# untitled.net
KiCad netlist of a schematic drawn in EAGLE
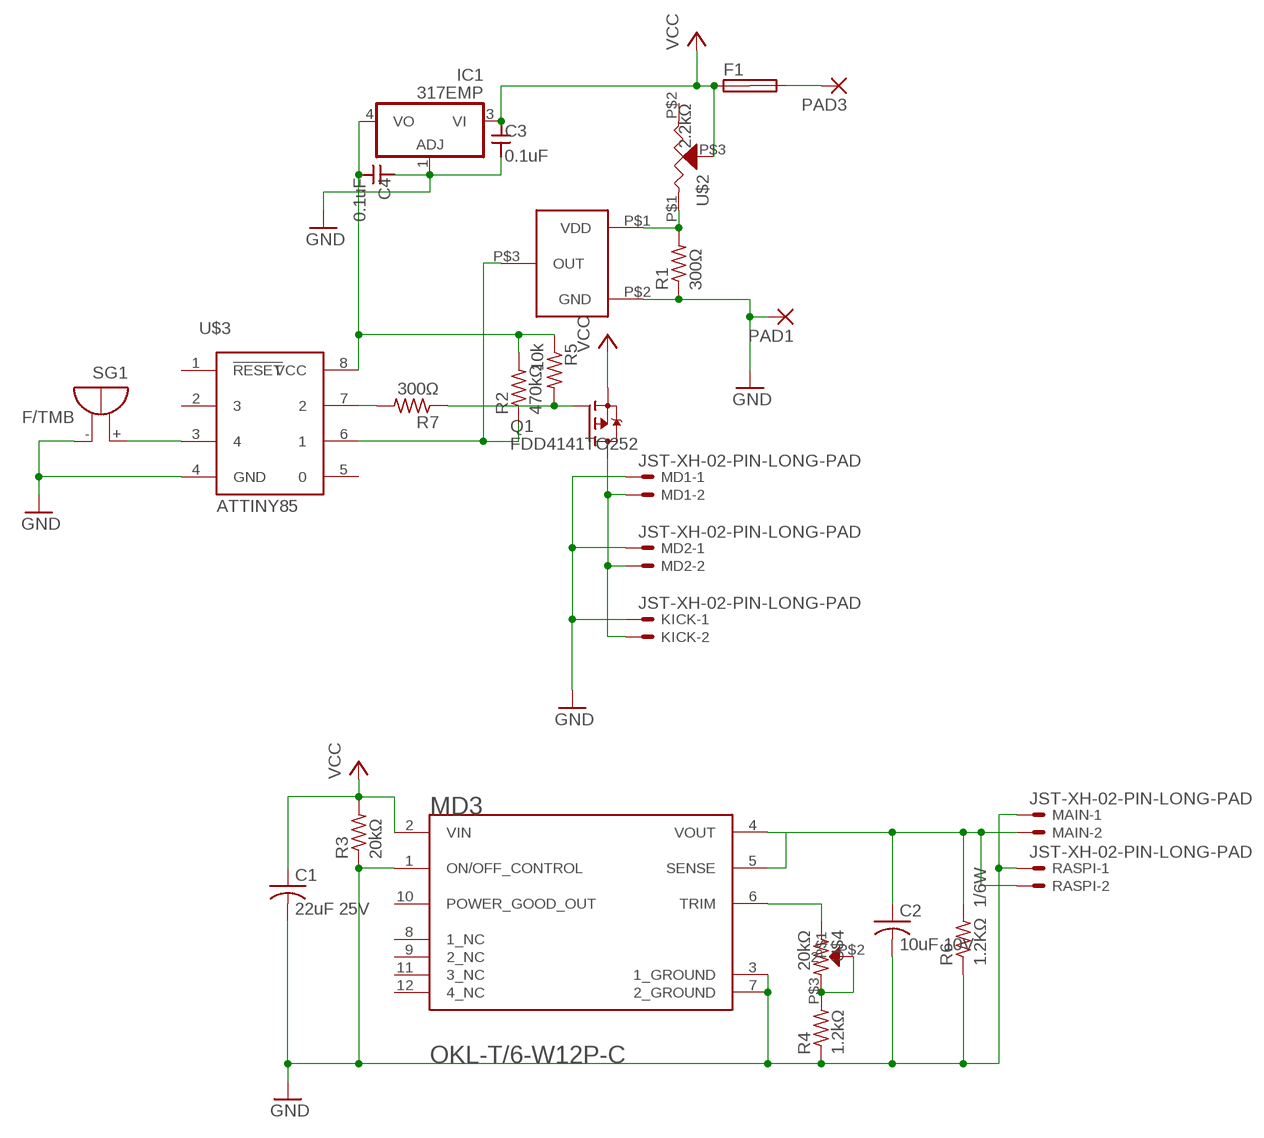
[diagram p0: schematic, sheet 1]

(export (version "E")
  (design (tool "Eeschema 10.0.6"))
  (components
    (comp (ref "C1")
      (value "22uF 25V")
      (footprint "eagle-import:C2012")
      (libsource (lib "eagle-import") (part "C-USC2012"))
    )
    (comp (ref "C2")
      (value "10uF 10V")
      (footprint "eagle-import:C2012")
      (libsource (lib "eagle-import") (part "C-USC2012"))
    )
    (comp (ref "C3")
      (value "0.1uF")
      (footprint "eagle-import:SMD1608")
      (libsource (lib "eagle-import") (part "CAPACITOR1608"))
    )
    (comp (ref "C4")
      (value "0.1uF")
      (footprint "eagle-import:SMD1608")
      (libsource (lib "eagle-import") (part "CAPACITOR1608"))
    )
    (comp (ref "F1")
      (value "SHK20L")
      (footprint "eagle-import:SHK20L")
      (libsource (lib "eagle-import") (part "SHK20L"))
    )
    (comp (ref "IC1")
      (value "317EMP")
      (footprint "eagle-import:SOT223")
      (libsource (lib "eagle-import") (part "317EMP"))
    )
    (comp (ref "KICK")
      (value "JST-XH-02-PIN-LONG-PAD")
      (footprint "eagle-import:JST-XH-02-PACKAGE-LONG-PAD")
      (libsource (lib "eagle-import") (part "JST-XH-02-PIN-LONG-PAD"))
    )
    (comp (ref "MAIN")
      (value "JST-XH-02-PIN-LONG-PAD")
      (footprint "eagle-import:JST-XH-02-PACKAGE-LONG-PAD")
      (libsource (lib "eagle-import") (part "JST-XH-02-PIN-LONG-PAD"))
    )
    (comp (ref "MD1")
      (value "JST-XH-02-PIN-LONG-PAD")
      (footprint "eagle-import:JST-XH-02-PACKAGE-LONG-PAD")
      (libsource (lib "eagle-import") (part "JST-XH-02-PIN-LONG-PAD"))
    )
    (comp (ref "MD2")
      (value "JST-XH-02-PIN-LONG-PAD")
      (footprint "eagle-import:JST-XH-02-PACKAGE-LONG-PAD")
      (libsource (lib "eagle-import") (part "JST-XH-02-PIN-LONG-PAD"))
    )
    (comp (ref "MD3")
      (value "OKL-T/6-W12P-CMURATA_OKL-T-6-W12P-C_0_0")
      (footprint "eagle-import:MURATA_OKL-T-6-W12P-C_0")
      (fields (field (name "MF") "Murata Power Solutions Inc.") (field (name "MP") "OKL-T/6-W12P-C"))
      (libsource (lib "eagle-import") (part "OKL-T/6-W12P-CMURATA_OKL-T-6-W12P-C_0_0"))
    )
    (comp (ref "PAD1")
      (value "3,81/1,4")
      (footprint "eagle-import:3,81_1,4")
      (libsource (lib "eagle-import") (part "3,81/1,4"))
    )
    (comp (ref "PAD3")
      (value "3,81/1,4")
      (footprint "eagle-import:3,81_1,4")
      (libsource (lib "eagle-import") (part "3,81/1,4"))
    )
    (comp (ref "Q1")
      (value "FDD4141TO252")
      (footprint "eagle-import:TO252")
      (libsource (lib "eagle-import") (part "FDD4141TO252"))
    )
    (comp (ref "R1")
      (value "300Ω")
      (footprint "eagle-import:M2012")
      (libsource (lib "eagle-import") (part "R-US_M2012"))
    )
    (comp (ref "R2")
      (value "470kΩ")
      (footprint "eagle-import:M2012")
      (libsource (lib "eagle-import") (part "R-US_M2012"))
    )
    (comp (ref "R3")
      (value "20kΩ")
      (footprint "eagle-import:M2012")
      (libsource (lib "eagle-import") (part "R-US_M2012"))
    )
    (comp (ref "R4")
      (value "1.2kΩ")
      (footprint "eagle-import:M2012")
      (libsource (lib "eagle-import") (part "R-US_M2012"))
    )
    (comp (ref "R5")
      (value "10k")
      (footprint "eagle-import:M2012")
      (libsource (lib "eagle-import") (part "R-US_M2012"))
    )
    (comp (ref "R6")
      (value "1.2KΩ 1/6W")
      (footprint "eagle-import:0805-THM")
      (libsource (lib "eagle-import") (part "FLIPFLOP-RES"))
    )
    (comp (ref "R7")
      (value "300Ω")
      (footprint "eagle-import:M2012")
      (libsource (lib "eagle-import") (part "R-US_M2012"))
    )
    (comp (ref "RASPI")
      (value "JST-XH-02-PIN-LONG-PAD")
      (footprint "eagle-import:JST-XH-02-PACKAGE-LONG-PAD")
      (libsource (lib "eagle-import") (part "JST-XH-02-PIN-LONG-PAD"))
    )
    (comp (ref "SG1")
      (value "F/TMB")
      (footprint "eagle-import:F_TMB")
      (libsource (lib "eagle-import") (part "F/TMB"))
    )
    (comp (ref "U$1")
      (value "R3111N211A")
      (footprint "eagle-import:R3111N211A")
      (libsource (lib "eagle-import") (part "R3111N211A"))
    )
    (comp (ref "U$2")
      (value "2.2kΩ")
      (footprint "eagle-import:SMD-R-TRIM")
      (libsource (lib "eagle-import") (part "SMD-R-TRIM"))
    )
    (comp (ref "U$3")
      (value "ATTINY85")
      (footprint "eagle-import:8P3")
      (libsource (lib "eagle-import") (part "ATTINY85"))
    )
    (comp (ref "U$4")
      (value "20kΩ")
      (footprint "eagle-import:R-TRIM")
      (libsource (lib "eagle-import") (part "R-TRIM"))
    )
  )
  (nets
    (net (code "1") (name "GND") (class "Default")
      (node (ref "C1") (pin "2") (pinfunction "2_2") (pintype "passive"))
      (node (ref "C2") (pin "2") (pinfunction "2_2") (pintype "passive"))
      (node (ref "C3") (pin "2") (pinfunction "2_2") (pintype "passive"))
      (node (ref "C4") (pin "1") (pinfunction "1_1") (pintype "passive"))
      (node (ref "IC1") (pin "1") (pinfunction "ADJ_1") (pintype "input"))
      (node (ref "KICK") (pin "1") (pinfunction "S_1") (pintype "passive"))
      (node (ref "MAIN") (pin "1") (pinfunction "S_1") (pintype "passive"))
      (node (ref "MD1") (pin "1") (pinfunction "S_1") (pintype "passive"))
      (node (ref "MD2") (pin "1") (pinfunction "S_1") (pintype "passive"))
      (node (ref "MD3") (pin "1") (pinfunction "ON/OFF_CONTROL_1") (pintype "input"))
      (node (ref "MD3") (pin "3") (pinfunction "1_GROUND_3") (pintype "power_in"))
      (node (ref "MD3") (pin "7") (pinfunction "2_GROUND_7") (pintype "power_in"))
      (node (ref "PAD1") (pin "1") (pinfunction "P_1") (pintype "passive"))
      (node (ref "R1") (pin "1") (pinfunction "1_1") (pintype "passive"))
      (node (ref "R3") (pin "1") (pinfunction "1_1") (pintype "passive"))
      (node (ref "R4") (pin "1") (pinfunction "1_1") (pintype "passive"))
      (node (ref "R6") (pin "1") (pinfunction "1_1") (pintype "passive"))
      (node (ref "RASPI") (pin "1") (pinfunction "S_1") (pintype "passive"))
      (node (ref "SG1") (pin "-") (pinfunction "-_-") (pintype "passive"))
      (node (ref "U$1") (pin "P$2") (pinfunction "GND_P$2") (pintype "bidirectional"))
      (node (ref "U$3") (pin "4") (pinfunction "GND_4") (pintype "power_in"))
    )
    (net (code "2") (name "Net-(IC1-VO)") (class "Default")
      (node (ref "C4") (pin "2") (pinfunction "2_2") (pintype "passive"))
      (node (ref "IC1") (pin "4") (pinfunction "VO_4") (pintype "passive"))
      (node (ref "R2") (pin "2") (pinfunction "2_2") (pintype "passive"))
      (node (ref "R5") (pin "1") (pinfunction "1_1") (pintype "passive"))
      (node (ref "U$3") (pin "8") (pinfunction "VCC_8") (pintype "power_in"))
    )
    (net (code "3") (name "Net-(KICKB-S)") (class "Default")
      (node (ref "KICK") (pin "2") (pinfunction "S_2") (pintype "passive"))
      (node (ref "MD1") (pin "2") (pinfunction "S_2") (pintype "passive"))
      (node (ref "MD2") (pin "2") (pinfunction "S_2") (pintype "passive"))
      (node (ref "Q1") (pin "3") (pinfunction "D_3") (pintype "passive"))
    )
    (net (code "4") (name "Net-(MAINB-S)") (class "Default")
      (node (ref "C2") (pin "1") (pinfunction "1_1") (pintype "passive"))
      (node (ref "MAIN") (pin "2") (pinfunction "S_2") (pintype "passive"))
      (node (ref "MD3") (pin "4") (pinfunction "VOUT_4") (pintype "power_in"))
      (node (ref "MD3") (pin "5") (pinfunction "SENSE_5") (pintype "passive"))
      (node (ref "R6") (pin "2") (pinfunction "2_2") (pintype "passive"))
      (node (ref "RASPI") (pin "2") (pinfunction "S_2") (pintype "passive"))
    )
    (net (code "5") (name "Net-(MD3-TRIM)") (class "Default")
      (node (ref "MD3") (pin "6") (pinfunction "TRIM_6") (pintype "passive"))
      (node (ref "U$4") (pin "P$1") (pinfunction "1_P$1") (pintype "passive"))
    )
    (net (code "6") (name "Net-(PAD3-P)") (class "Default")
      (node (ref "F1") (pin "2A") (pinfunction "2A_2A") (pintype "passive"))
      (node (ref "PAD3") (pin "1") (pinfunction "P_1") (pintype "passive"))
    )
    (net (code "7") (name "Net-(Q1-G)") (class "Default")
      (node (ref "Q1") (pin "1") (pinfunction "G_1") (pintype "passive"))
      (node (ref "R5") (pin "2") (pinfunction "2_2") (pintype "passive"))
      (node (ref "R7") (pin "1") (pinfunction "1_1") (pintype "passive"))
    )
    (net (code "8") (name "Net-(U$1-OUT)") (class "Default")
      (node (ref "R2") (pin "1") (pinfunction "1_1") (pintype "passive"))
      (node (ref "U$1") (pin "P$3") (pinfunction "OUT_P$3") (pintype "bidirectional"))
      (node (ref "U$3") (pin "6") (pinfunction "1_6") (pintype "bidirectional"))
    )
    (net (code "9") (name "Net-(U$1-VDD)") (class "Default")
      (node (ref "R1") (pin "2") (pinfunction "2_2") (pintype "passive"))
      (node (ref "U$1") (pin "P$1") (pinfunction "VDD_P$1") (pintype "bidirectional"))
      (node (ref "U$2") (pin "P$1") (pinfunction "3_P$1") (pintype "passive"))
    )
    (net (code "10") (name "Net-(U$3-2)") (class "Default")
      (node (ref "R7") (pin "2") (pinfunction "2_2") (pintype "passive"))
      (node (ref "U$3") (pin "7") (pinfunction "2_7") (pintype "bidirectional"))
    )
    (net (code "11") (name "Net-(U$3-4)") (class "Default")
      (node (ref "SG1") (pin "+") (pinfunction "+_+") (pintype "passive"))
      (node (ref "U$3") (pin "3") (pinfunction "4_3") (pintype "bidirectional"))
    )
    (net (code "12") (name "Net-(U$4-2)") (class "Default")
      (node (ref "R4") (pin "2") (pinfunction "2_2") (pintype "passive"))
      (node (ref "U$4") (pin "P$2") (pinfunction "2_P$2") (pintype "bidirectional"))
      (node (ref "U$4") (pin "P$3") (pinfunction "P$1_P$3") (pintype "bidirectional"))
    )
    (net (code "13") (name "VCC") (class "Default")
      (node (ref "C1") (pin "1") (pinfunction "1_1") (pintype "passive"))
      (node (ref "C3") (pin "1") (pinfunction "1_1") (pintype "passive"))
      (node (ref "F1") (pin "1A") (pinfunction "1A_1A") (pintype "passive"))
      (node (ref "IC1") (pin "3") (pinfunction "VI_3") (pintype "input"))
      (node (ref "MD3") (pin "2") (pinfunction "VIN_2") (pintype "power_in"))
      (node (ref "Q1") (pin "2") (pinfunction "S_2") (pintype "passive"))
      (node (ref "R3") (pin "2") (pinfunction "2_2") (pintype "passive"))
      (node (ref "U$2") (pin "P$3") (pinfunction "2_P$3") (pintype "passive"))
    )
    (net (code "14") (name "unconnected-(F1-Pad1B)") (class "Default")
      (node (ref "F1") (pin "1B") (pinfunction "1B_1B") (pintype "passive"))
    )
    (net (code "15") (name "unconnected-(F1-Pad2B)") (class "Default")
      (node (ref "F1") (pin "2B") (pinfunction "2B_2B") (pintype "passive"))
    )
    (net (code "16") (name "unconnected-(MD3-1_NC-Pad8)") (class "Default")
      (node (ref "MD3") (pin "8") (pinfunction "1_NC_8") (pintype "passive"))
    )
    (net (code "17") (name "unconnected-(MD3-2_NC-Pad9)") (class "Default")
      (node (ref "MD3") (pin "9") (pinfunction "2_NC_9") (pintype "passive"))
    )
    (net (code "18") (name "unconnected-(MD3-3_NC-Pad11)") (class "Default")
      (node (ref "MD3") (pin "11") (pinfunction "3_NC_11") (pintype "passive"))
    )
    (net (code "19") (name "unconnected-(MD3-4_NC-Pad12)") (class "Default")
      (node (ref "MD3") (pin "12") (pinfunction "4_NC_12") (pintype "passive"))
    )
    (net (code "20") (name "unconnected-(MD3-POWER_GOOD_OUT-Pad10)") (class "Default")
      (node (ref "MD3") (pin "10") (pinfunction "POWER_GOOD_OUT_10") (pintype "open_collector"))
    )
    (net (code "21") (name "unconnected-(U$2-1-PadP$2)") (class "Default")
      (node (ref "U$2") (pin "P$2") (pinfunction "1_P$2") (pintype "passive"))
    )
    (net (code "22") (name "unconnected-(U$3-0-Pad5)") (class "Default")
      (node (ref "U$3") (pin "5") (pinfunction "0_5") (pintype "bidirectional"))
    )
    (net (code "23") (name "unconnected-(U$3-3-Pad2)") (class "Default")
      (node (ref "U$3") (pin "2") (pinfunction "3_2") (pintype "bidirectional"))
    )
    (net (code "24") (name "unconnected-(U$3-~{RESET}-Pad1)") (class "Default")
      (node (ref "U$3") (pin "1") (pinfunction "~{RESET}_1") (pintype "bidirectional"))
    )
  )
)
